# USB2UART.net
KiCad netlist of a schematic drawn in Altium Designer
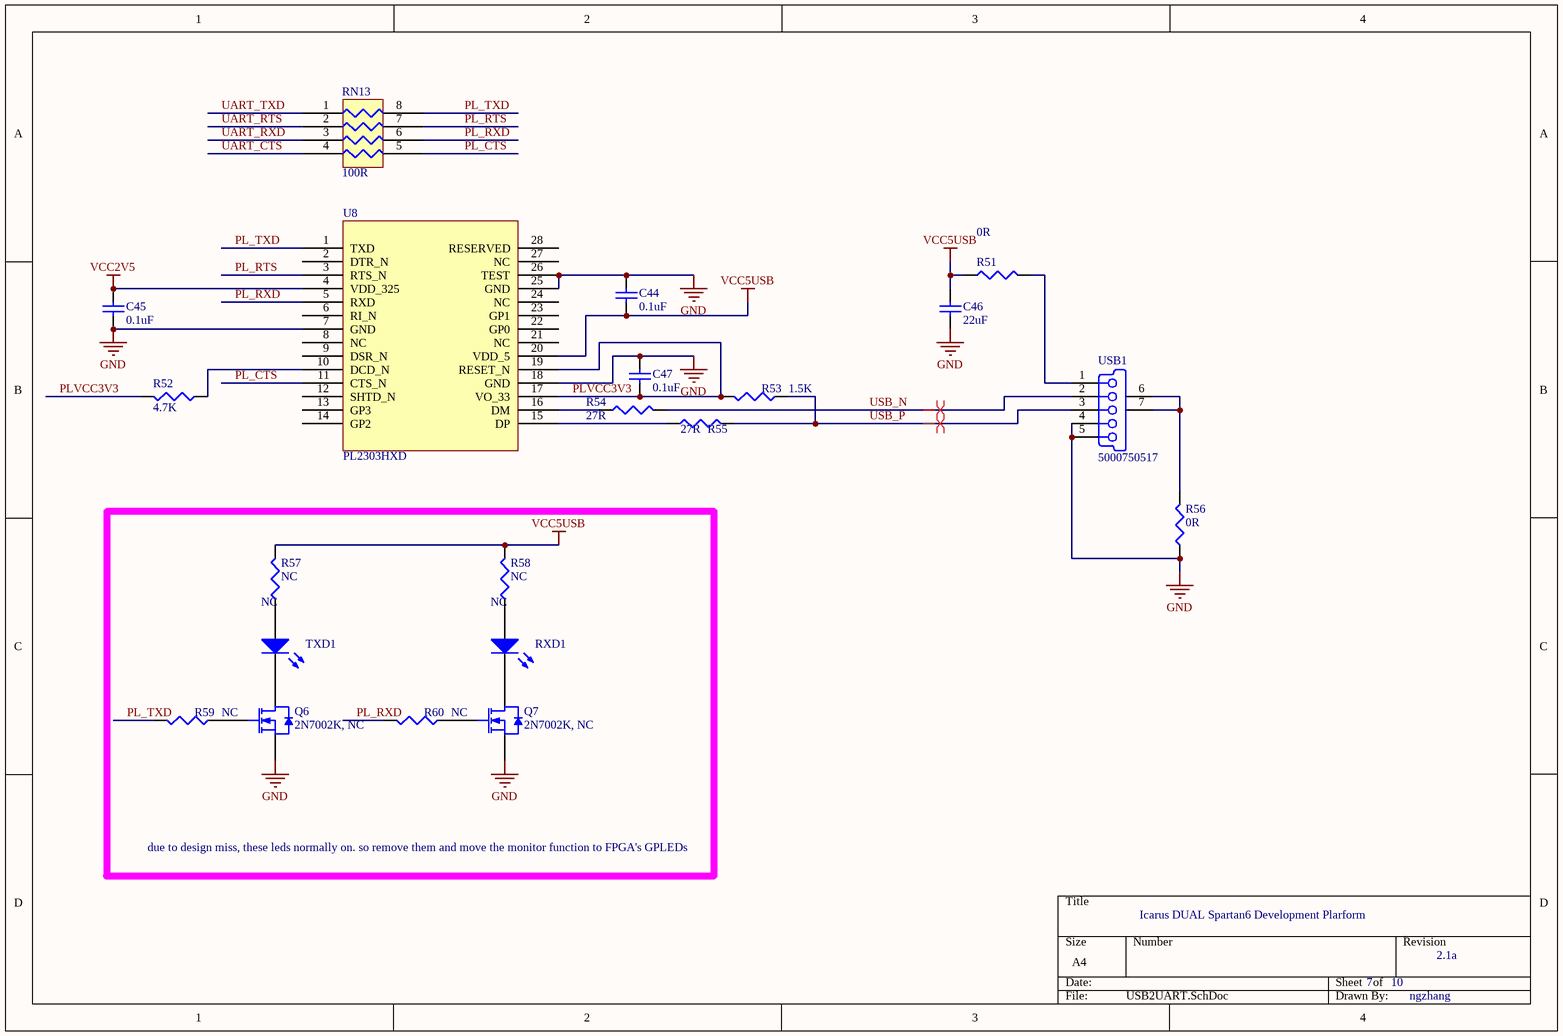
[diagram p0: USB2UART.SchDoc]

(export (version "E")
  (design (tool "Eeschema 10.0.6"))
  (components
    (comp (ref "C44")
      (value "0.1uF")
      (footprint "1608[0603]")
      (description "Capacitor (Semiconductor SIM Model)")
      (fields (field (name "PUBLISHER") "Altium Limited"))
      (libsource (lib "Miscellaneous Devices") (part "Cap Semi"))
    )
    (comp (ref "C45")
      (value "0.1uF")
      (footprint "1608[0603]")
      (description "Capacitor (Semiconductor SIM Model)")
      (fields (field (name "PUBLISHER") "Altium Limited"))
      (libsource (lib "Miscellaneous Devices") (part "Cap Semi"))
    )
    (comp (ref "C46")
      (value "22uF")
      (footprint "C1206")
      (description "Capacitor (Semiconductor SIM Model)")
      (fields (field (name "PUBLISHER") "Altium Limited"))
      (libsource (lib "Miscellaneous Devices") (part "Cap Semi"))
    )
    (comp (ref "C47")
      (value "0.1uF")
      (footprint "1608[0603]")
      (description "Capacitor (Semiconductor SIM Model)")
      (fields (field (name "PUBLISHER") "Altium Limited"))
      (libsource (lib "Miscellaneous Devices") (part "Cap Semi"))
    )
    (comp (ref "Q6")
      (value "2N7002K, NC")
      (footprint "SOT23_N")
      (description "N-channel Enhancement Mode Field-effect Transistor")
      (fields (field (name "PUBLISHER") "Altium Limited"))
      (libsource (lib "Philips Discrete MOSFET - Low Power") (part "2N7002"))
    )
    (comp (ref "Q7")
      (value "2N7002K, NC")
      (footprint "SOT23_N")
      (description "N-channel Enhancement Mode Field-effect Transistor")
      (fields (field (name "PUBLISHER") "Altium Limited"))
      (libsource (lib "Philips Discrete MOSFET - Low Power") (part "2N7002"))
    )
    (comp (ref "R51")
      (value "0R")
      (footprint "J1-0603")
      (description "Resistor")
      (fields (field (name "PUBLISHER") "Altium Limited"))
      (libsource (lib "Miscellaneous Devices") (part "Res3"))
    )
    (comp (ref "R52")
      (value "4.7K")
      (footprint "J1-0603")
      (description "Resistor")
      (fields (field (name "PUBLISHER") "Altium Limited"))
      (libsource (lib "Miscellaneous Devices") (part "Res3"))
    )
    (comp (ref "R53")
      (value "1.5K")
      (footprint "J1-0603")
      (description "Resistor")
      (fields (field (name "PUBLISHER") "Altium Limited"))
      (libsource (lib "Miscellaneous Devices") (part "Res3"))
    )
    (comp (ref "R54")
      (value "27R")
      (footprint "J1-0603")
      (description "Resistor")
      (fields (field (name "PUBLISHER") "Altium Limited"))
      (libsource (lib "Miscellaneous Devices") (part "Res3"))
    )
    (comp (ref "R55")
      (value "27R")
      (footprint "J1-0603")
      (description "Resistor")
      (fields (field (name "PUBLISHER") "Altium Limited"))
      (libsource (lib "Miscellaneous Devices") (part "Res3"))
    )
    (comp (ref "R56")
      (value "0R")
      (footprint "J1-0603")
      (description "Resistor")
      (fields (field (name "PUBLISHER") "Altium Limited"))
      (libsource (lib "Miscellaneous Devices") (part "Res3"))
    )
    (comp (ref "R57")
      (value "NC")
      (footprint "J1-0603")
      (description "Resistor")
      (fields (field (name "PUBLISHER") "Altium Limited"))
      (libsource (lib "Miscellaneous Devices") (part "Res3"))
    )
    (comp (ref "R58")
      (value "NC")
      (footprint "J1-0603")
      (description "Resistor")
      (fields (field (name "PUBLISHER") "Altium Limited"))
      (libsource (lib "Miscellaneous Devices") (part "Res3"))
    )
    (comp (ref "R59")
      (value "NC")
      (footprint "J1-0603")
      (description "Resistor")
      (fields (field (name "PUBLISHER") "Altium Limited"))
      (libsource (lib "Miscellaneous Devices") (part "Res3"))
    )
    (comp (ref "R60")
      (value "NC")
      (footprint "J1-0603")
      (description "Resistor")
      (fields (field (name "PUBLISHER") "Altium Limited"))
      (libsource (lib "Miscellaneous Devices") (part "Res3"))
    )
    (comp (ref "RN13") (value "100R") (footprint "EXBV8V") (libsource (lib "S6") (part "RES4PACK")))
    (comp (ref "RXD1")
      (value "NC")
      (footprint "CD1608-0603")
      (description "Typical BLUE SiC LED")
      (fields (field (name "PUBLISHER") "Altium Limited"))
      (libsource (lib "Miscellaneous Devices") (part "LED3"))
    )
    (comp (ref "TXD1")
      (value "NC")
      (footprint "CD1608-0603")
      (description "Typical BLUE SiC LED")
      (fields (field (name "PUBLISHER") "Altium Limited"))
      (libsource (lib "Miscellaneous Devices") (part "LED3"))
    )
    (comp (ref "U8") (value "PL2303HXD") (footprint "SSOP28_N") (libsource (lib "S6") (part "PL2303")))
    (comp (ref "USB1")
      (value "5000750517")
      (footprint "5000750517")
      (fields (field (name "PUBLISHER") "Altium Limited"))
      (libsource (lib "Molex Serial Bus Mini USB") (part "5000750517"))
    )
  )
  (nets
    (net (code "1") (name "/PLVCC3V3") (class "Default")
      (node (ref "C47") (pin "1") (pinfunction "1_1") (pintype "passive"))
      (node (ref "R52") (pin "2") (pinfunction "2_2") (pintype "passive"))
      (node (ref "R53") (pin "2") (pinfunction "2_2") (pintype "passive"))
      (node (ref "U8") (pin "17") (pinfunction "VO_33_17") (pintype "power_in"))
      (node (ref "U8") (pin "19") (pinfunction "RESET_N_19") (pintype "power_in"))
    )
    (net (code "2") (name "/PL_CTS") (class "Default")
      (node (ref "RN13") (pin "5") (pinfunction "5_5") (pintype "power_in"))
      (node (ref "U8") (pin "11") (pinfunction "CTS_N_11") (pintype "power_in"))
    )
    (net (code "3") (name "/PL_RTS") (class "Default")
      (node (ref "RN13") (pin "7") (pinfunction "7_7") (pintype "power_in"))
      (node (ref "U8") (pin "3") (pinfunction "RTS_N_3") (pintype "power_in"))
    )
    (net (code "4") (name "/PL_RXD") (class "Default")
      (node (ref "R60") (pin "2") (pinfunction "2_2") (pintype "passive"))
      (node (ref "RN13") (pin "6") (pinfunction "6_6") (pintype "power_in"))
      (node (ref "U8") (pin "5") (pinfunction "RXD_5") (pintype "power_in"))
    )
    (net (code "5") (name "/PL_TXD") (class "Default")
      (node (ref "R59") (pin "2") (pinfunction "2_2") (pintype "passive"))
      (node (ref "RN13") (pin "8") (pinfunction "8_8") (pintype "power_in"))
      (node (ref "U8") (pin "1") (pinfunction "TXD_1") (pintype "power_in"))
    )
    (net (code "6") (name "/UART_CTS") (class "Default")
      (node (ref "RN13") (pin "4") (pinfunction "4_4") (pintype "power_in"))
    )
    (net (code "7") (name "/UART_RTS") (class "Default")
      (node (ref "RN13") (pin "2") (pinfunction "2_2") (pintype "power_in"))
    )
    (net (code "8") (name "/UART_RXD") (class "Default")
      (node (ref "RN13") (pin "3") (pinfunction "3_3") (pintype "power_in"))
    )
    (net (code "9") (name "/UART_TXD") (class "Default")
      (node (ref "RN13") (pin "1") (pinfunction "1_1") (pintype "power_in"))
    )
    (net (code "10") (name "/USB_N") (class "Default")
      (node (ref "R54") (pin "2") (pinfunction "2_2") (pintype "passive"))
      (node (ref "USB1") (pin "2") (pinfunction "D-_2") (pintype "passive"))
    )
    (net (code "11") (name "/USB_P") (class "Default")
      (node (ref "R53") (pin "1") (pinfunction "1_1") (pintype "passive"))
      (node (ref "R55") (pin "2") (pinfunction "2_2") (pintype "passive"))
      (node (ref "USB1") (pin "3") (pinfunction "D+_3") (pintype "passive"))
    )
    (net (code "12") (name "GND") (class "Default")
      (node (ref "C44") (pin "2") (pinfunction "2_2") (pintype "passive"))
      (node (ref "C45") (pin "1") (pinfunction "1_1") (pintype "passive"))
      (node (ref "C46") (pin "1") (pinfunction "1_1") (pintype "passive"))
      (node (ref "C47") (pin "2") (pinfunction "2_2") (pintype "passive"))
      (node (ref "Q6") (pin "2") (pinfunction "S_2") (pintype "passive"))
      (node (ref "Q7") (pin "2") (pinfunction "S_2") (pintype "passive"))
      (node (ref "R56") (pin "1") (pinfunction "1_1") (pintype "passive"))
      (node (ref "U8") (pin "18") (pinfunction "GND_18") (pintype "power_in"))
      (node (ref "U8") (pin "25") (pinfunction "GND_25") (pintype "power_in"))
      (node (ref "U8") (pin "26") (pinfunction "TEST_26") (pintype "power_in"))
      (node (ref "U8") (pin "7") (pinfunction "GND_7") (pintype "power_in"))
      (node (ref "USB1") (pin "4") (pinfunction "ID_4") (pintype "passive"))
      (node (ref "USB1") (pin "5") (pinfunction "GND_5") (pintype "passive"))
    )
    (net (code "13") (name "Net-(Q6-D)") (class "Default")
      (node (ref "Q6") (pin "3") (pinfunction "D_3") (pintype "passive"))
      (node (ref "TXD1") (pin "2") (pinfunction "K_2") (pintype "passive"))
    )
    (net (code "14") (name "Net-(Q6-G)") (class "Default")
      (node (ref "Q6") (pin "1") (pinfunction "G_1") (pintype "passive"))
      (node (ref "R59") (pin "1") (pinfunction "1_1") (pintype "passive"))
    )
    (net (code "15") (name "Net-(Q7-D)") (class "Default")
      (node (ref "Q7") (pin "3") (pinfunction "D_3") (pintype "passive"))
      (node (ref "RXD1") (pin "2") (pinfunction "K_2") (pintype "passive"))
    )
    (net (code "16") (name "Net-(Q7-G)") (class "Default")
      (node (ref "Q7") (pin "1") (pinfunction "G_1") (pintype "passive"))
      (node (ref "R60") (pin "1") (pinfunction "1_1") (pintype "passive"))
    )
    (net (code "17") (name "Net-(RXD1-A)") (class "Default")
      (node (ref "R58") (pin "1") (pinfunction "1_1") (pintype "passive"))
      (node (ref "RXD1") (pin "1") (pinfunction "A_1") (pintype "passive"))
    )
    (net (code "18") (name "Net-(TXD1-A)") (class "Default")
      (node (ref "R57") (pin "1") (pinfunction "1_1") (pintype "passive"))
      (node (ref "TXD1") (pin "1") (pinfunction "A_1") (pintype "passive"))
    )
    (net (code "19") (name "Net-(U8-DCD_N)") (class "Default")
      (node (ref "R52") (pin "1") (pinfunction "1_1") (pintype "passive"))
      (node (ref "U8") (pin "10") (pinfunction "DCD_N_10") (pintype "power_in"))
    )
    (net (code "20") (name "Net-(U8-DM)") (class "Default")
      (node (ref "R54") (pin "1") (pinfunction "1_1") (pintype "passive"))
      (node (ref "U8") (pin "16") (pinfunction "DM_16") (pintype "power_in"))
    )
    (net (code "21") (name "Net-(U8-DP)") (class "Default")
      (node (ref "R55") (pin "1") (pinfunction "1_1") (pintype "passive"))
      (node (ref "U8") (pin "15") (pinfunction "DP_15") (pintype "power_in"))
    )
    (net (code "22") (name "Net-(USB1-MH1)") (class "Default")
      (node (ref "R56") (pin "2") (pinfunction "2_2") (pintype "passive"))
      (node (ref "USB1") (pin "6") (pinfunction "MH1_6") (pintype "passive"))
      (node (ref "USB1") (pin "7") (pinfunction "MH2_7") (pintype "passive"))
    )
    (net (code "23") (name "Net-(USB1-V_BUS)") (class "Default")
      (node (ref "R51") (pin "2") (pinfunction "2_2") (pintype "passive"))
      (node (ref "USB1") (pin "1") (pinfunction "V_BUS_1") (pintype "passive"))
    )
    (net (code "24") (name "VCC2V5") (class "Default")
      (node (ref "C45") (pin "2") (pinfunction "2_2") (pintype "passive"))
      (node (ref "U8") (pin "4") (pinfunction "VDD_325_4") (pintype "power_in"))
    )
    (net (code "25") (name "VCC5USB") (class "Default")
      (node (ref "C44") (pin "1") (pinfunction "1_1") (pintype "passive"))
      (node (ref "C46") (pin "2") (pinfunction "2_2") (pintype "passive"))
      (node (ref "R51") (pin "1") (pinfunction "1_1") (pintype "passive"))
      (node (ref "R57") (pin "2") (pinfunction "2_2") (pintype "passive"))
      (node (ref "R58") (pin "2") (pinfunction "2_2") (pintype "passive"))
      (node (ref "U8") (pin "20") (pinfunction "VDD_5_20") (pintype "power_in"))
    )
    (net (code "26") (name "unconnected-(U8-DSR_N-Pad9)") (class "Default")
      (node (ref "U8") (pin "9") (pinfunction "DSR_N_9") (pintype "power_in"))
    )
    (net (code "27") (name "unconnected-(U8-DTR_N-Pad2)") (class "Default")
      (node (ref "U8") (pin "2") (pinfunction "DTR_N_2") (pintype "power_in"))
    )
    (net (code "28") (name "unconnected-(U8-GP0-Pad22)") (class "Default")
      (node (ref "U8") (pin "22") (pinfunction "GP0_22") (pintype "power_in"))
    )
    (net (code "29") (name "unconnected-(U8-GP1-Pad23)") (class "Default")
      (node (ref "U8") (pin "23") (pinfunction "GP1_23") (pintype "power_in"))
    )
    (net (code "30") (name "unconnected-(U8-GP2-Pad14)") (class "Default")
      (node (ref "U8") (pin "14") (pinfunction "GP2_14") (pintype "power_in"))
    )
    (net (code "31") (name "unconnected-(U8-GP3-Pad13)") (class "Default")
      (node (ref "U8") (pin "13") (pinfunction "GP3_13") (pintype "power_in"))
    )
    (net (code "32") (name "unconnected-(U8-NC-Pad8)") (class "Default")
      (node (ref "U8") (pin "8") (pinfunction "NC_8") (pintype "power_in"))
    )
    (net (code "33") (name "unconnected-(U8-NC-Pad21)") (class "Default")
      (node (ref "U8") (pin "21") (pinfunction "NC_21") (pintype "power_in"))
    )
    (net (code "34") (name "unconnected-(U8-NC-Pad24)") (class "Default")
      (node (ref "U8") (pin "24") (pinfunction "NC_24") (pintype "power_in"))
    )
    (net (code "35") (name "unconnected-(U8-NC-Pad27)") (class "Default")
      (node (ref "U8") (pin "27") (pinfunction "NC_27") (pintype "power_in"))
    )
    (net (code "36") (name "unconnected-(U8-RESERVED-Pad28)") (class "Default")
      (node (ref "U8") (pin "28") (pinfunction "RESERVED_28") (pintype "power_in"))
    )
    (net (code "37") (name "unconnected-(U8-RI_N-Pad6)") (class "Default")
      (node (ref "U8") (pin "6") (pinfunction "RI_N_6") (pintype "power_in"))
    )
    (net (code "38") (name "unconnected-(U8-SHTD_N-Pad12)") (class "Default")
      (node (ref "U8") (pin "12") (pinfunction "SHTD_N_12") (pintype "power_in"))
    )
  )
)
